# SCH_Moonshine_std_2026-02-26.net
KiCad netlist of a schematic drawn in EasyEDA
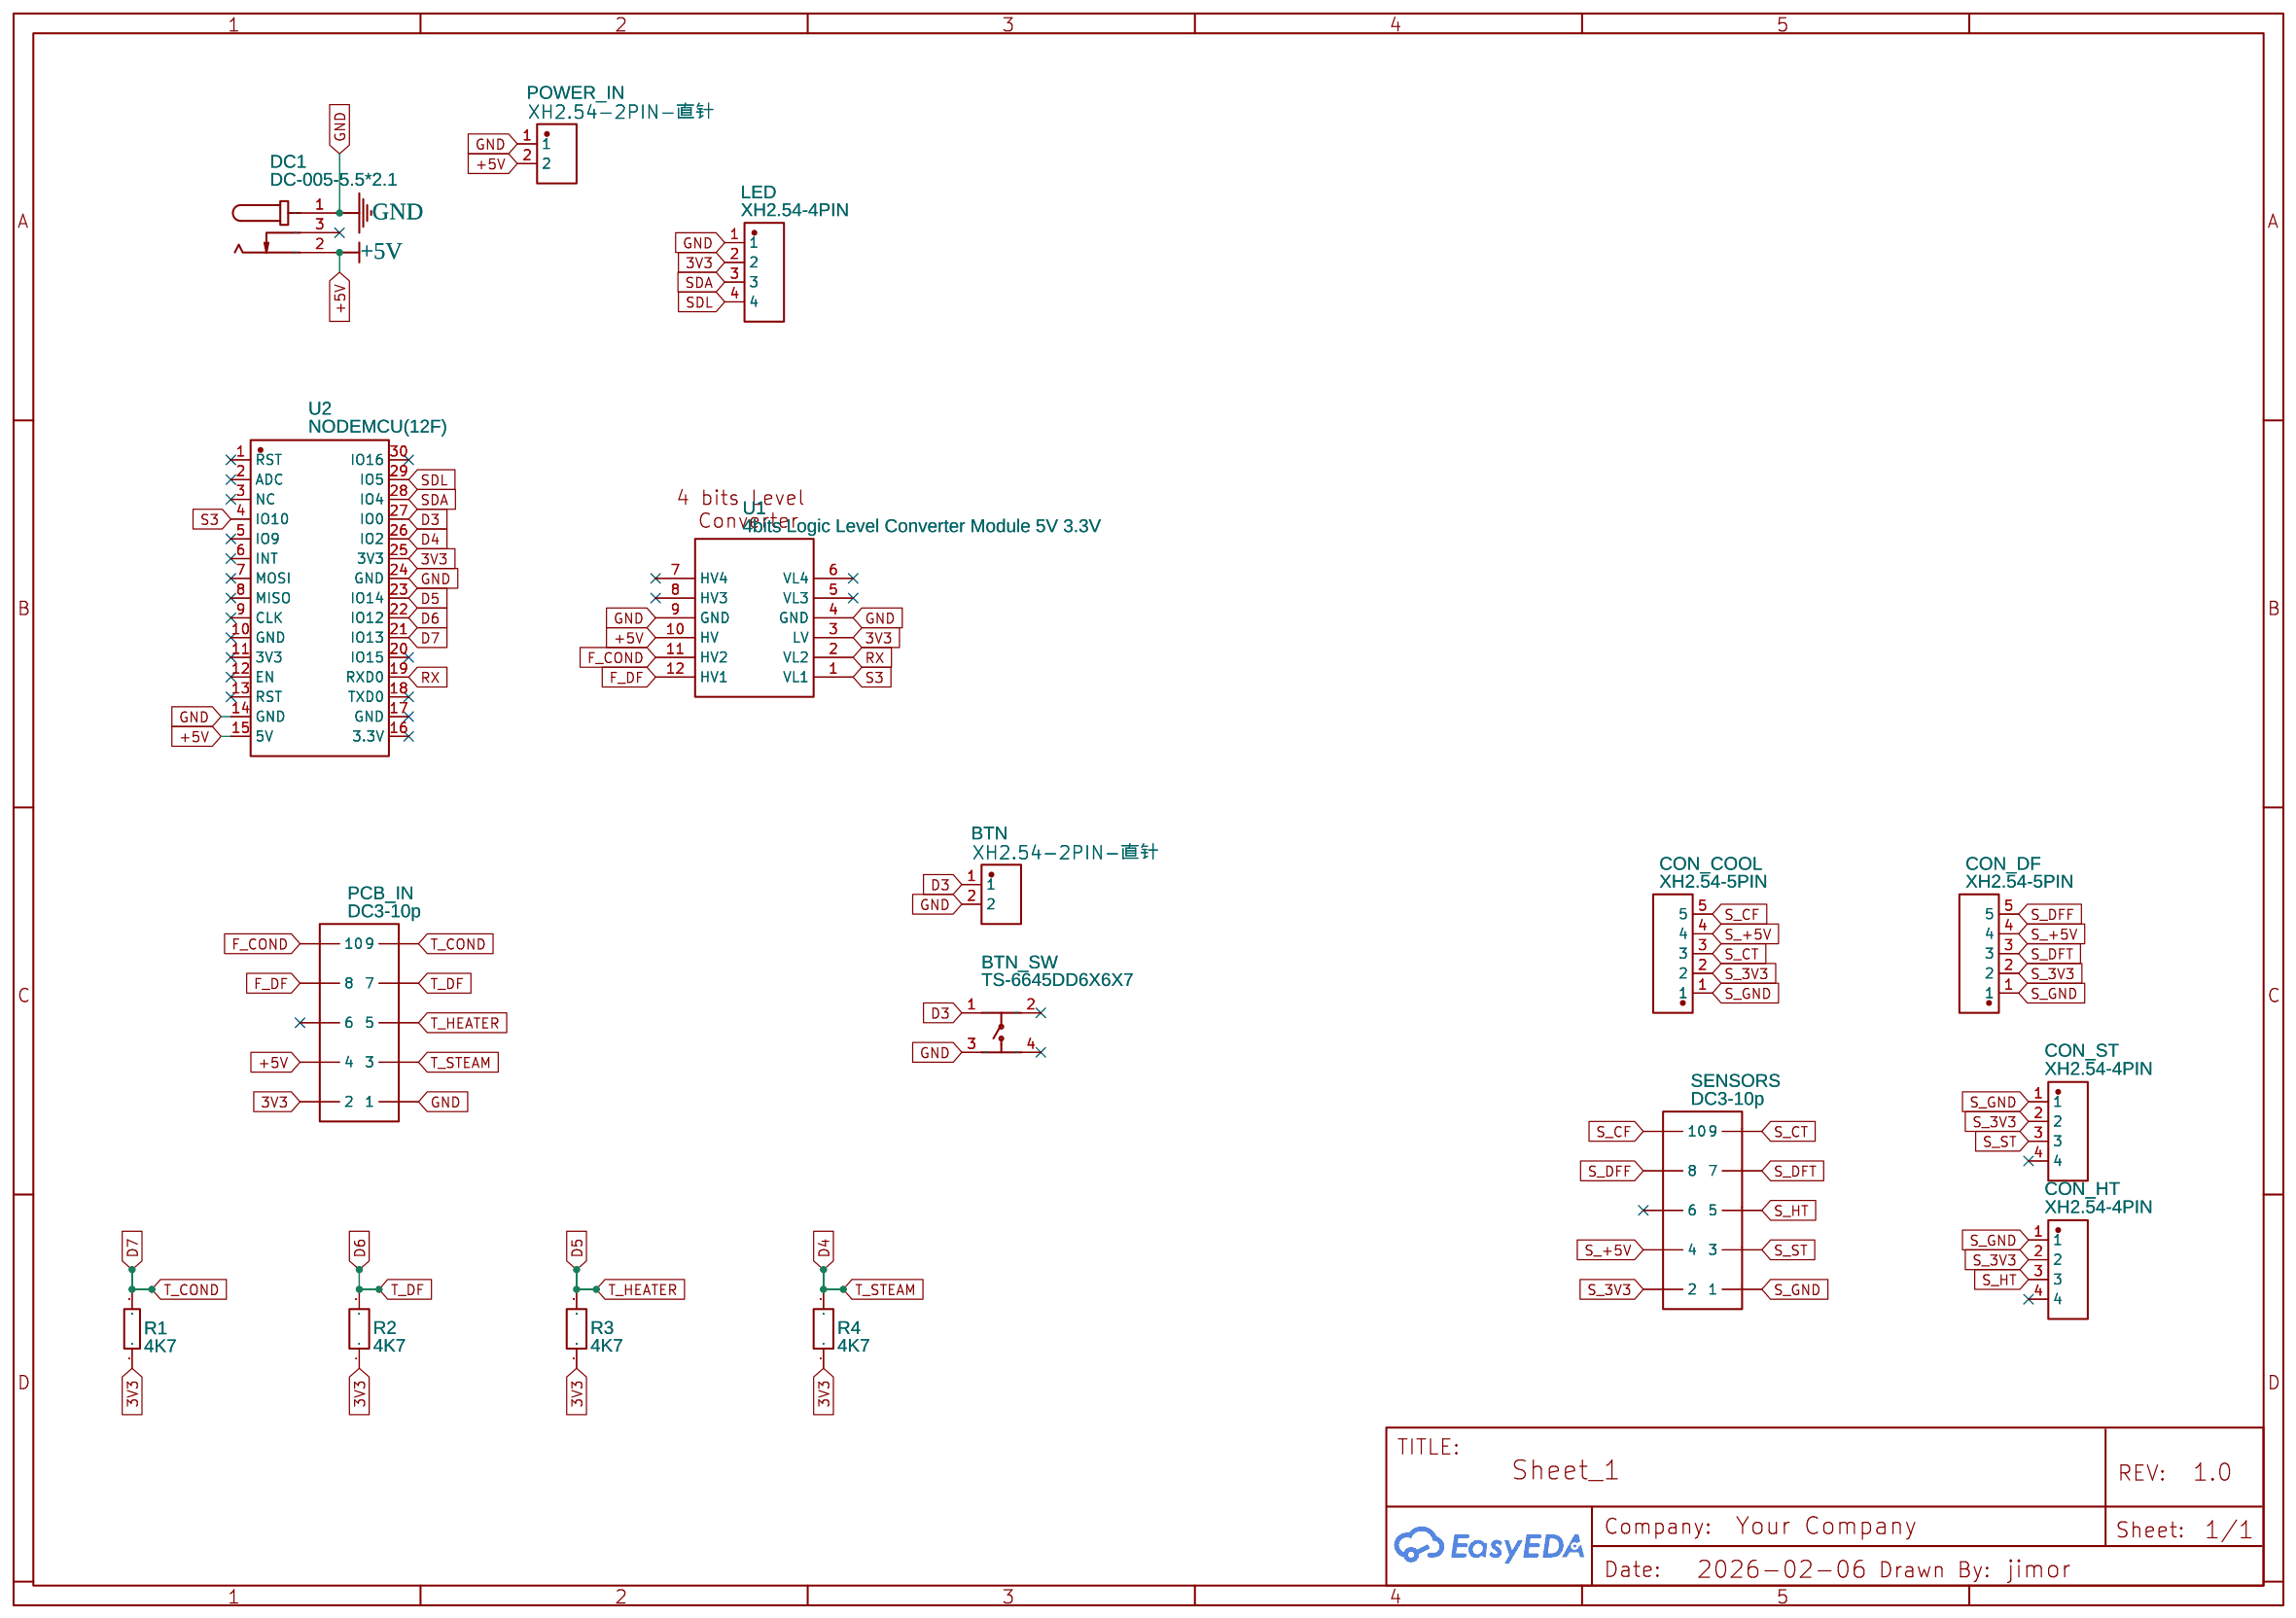
[diagram p0: schematic sheet]

(export (version "E")
  (design (tool "Eeschema 10.0.6"))
  (components
    (comp (ref "BTN") (value "XH2.54-2PIN-直针") (libsource (lib "") (part "XH2.54-2PIN-直针_1")))
    (comp (ref "BTN_SW")
      (value "TS-6645DD6X6X7")
      (fields (field (name "Manufacturer Part") "TS-6645DD6x6x7") (field (name "Manufacturer") "CAX(创都)"))
      (libsource (lib "") (part "TS-6645DD6X6X7"))
    )
    (comp (ref "CON_COOL")
      (value "XH2.54-5PIN")
      (fields (field (name "Manufacturer Part") "PZ254V-11-05P") (field (name "Manufacturer") "XFCN(兴飞)"))
      (libsource (lib "") (part "HDR-TH-2.54-1ROW-5PIN-39MIL-FRUITLOOP57"))
    )
    (comp (ref "CON_DF")
      (value "XH2.54-5PIN")
      (fields (field (name "Manufacturer Part") "PZ254V-11-05P") (field (name "Manufacturer") "XFCN(兴飞)"))
      (libsource (lib "") (part "HDR-TH-2.54-1ROW-5PIN-39MIL-FRUITLOOP57_1"))
    )
    (comp (ref "CON_HT") (value "XH2.54-4PIN") (libsource (lib "") (part "XH2.54-4PIN")))
    (comp (ref "CON_ST") (value "XH2.54-4PIN") (libsource (lib "") (part "XH2.54-4PIN_1")))
    (comp (ref "DC1") (value "DC-005-5.5*2.1") (libsource (lib "") (part "DC-005-5.5*2.1")))
    (comp (ref "LED") (value "XH2.54-4PIN") (libsource (lib "") (part "XH2.54-4PIN_2")))
    (comp (ref "PCB_IN") (value "DC3-10p") (libsource (lib "") (part "DC3-10p_1")))
    (comp (ref "POWER_IN") (value "XH2.54-2PIN-直针") (libsource (lib "") (part "XH2.54-2PIN-直针")))
    (comp (ref "R1")
      (value "4K7")
      (fields (field (name "Manufacturer Part") "AXIAL-0.4"))
      (libsource (lib "") (part "AXIAL-0.4"))
    )
    (comp (ref "R2")
      (value "4K7")
      (fields (field (name "Manufacturer Part") "3.3K-AXIAL-3.0") (field (name "Manufacturer") "睿思电阻"))
      (libsource (lib "") (part "3.3K-AXIAL-3.0"))
    )
    (comp (ref "R3")
      (value "4K7")
      (fields (field (name "Manufacturer Part") "3.3K-AXIAL-3.0") (field (name "Manufacturer") "睿思电阻"))
      (libsource (lib "") (part "3.3K-AXIAL-3.0"))
    )
    (comp (ref "R4")
      (value "4K7")
      (fields (field (name "Manufacturer Part") "3.3K-AXIAL-3.0") (field (name "Manufacturer") "睿思电阻"))
      (libsource (lib "") (part "3.3K-AXIAL-3.0"))
    )
    (comp (ref "SENSORS") (value "DC3-10p") (libsource (lib "") (part "DC3-10p")))
    (comp (ref "U1")
      (value "4bits Logic Level Converter Module 5V 3.3V")
      (libsource (lib "") (part "4bits Logic Level Converter Module 5V 3.3V"))
    )
    (comp (ref "U2")
      (value "NODEMCU(12F)")
      (fields (field (name "Manufacturer") "Ai-Thinker(安信可)"))
      (libsource (lib "") (part "NODEMCU(12F)"))
    )
  )
  (nets
    (net (code "1") (name "+5V") (class "Default")
      (node (ref "DC1") (pin "2") (pinfunction "2_2") (pintype "unspecified"))
      (node (ref "PCB_IN") (pin "4") (pinfunction "4_4") (pintype "unspecified"))
      (node (ref "POWER_IN") (pin "2") (pinfunction "2_2") (pintype "unspecified"))
      (node (ref "U1") (pin "10") (pinfunction "HV_10") (pintype "unspecified"))
      (node (ref "U2") (pin "15") (pinfunction "5V_15") (pintype "unspecified"))
    )
    (net (code "2") (name "3V3") (class "Default")
      (node (ref "LED") (pin "2") (pinfunction "2_2") (pintype "unspecified"))
      (node (ref "PCB_IN") (pin "2") (pinfunction "2_2") (pintype "unspecified"))
      (node (ref "R1") (pin "1") (pinfunction "1_1") (pintype "unspecified"))
      (node (ref "R2") (pin "1") (pinfunction "1_1") (pintype "unspecified"))
      (node (ref "R3") (pin "1") (pinfunction "1_1") (pintype "unspecified"))
      (node (ref "R4") (pin "1") (pinfunction "1_1") (pintype "unspecified"))
      (node (ref "U1") (pin "3") (pinfunction "LV_3") (pintype "unspecified"))
      (node (ref "U2") (pin "25") (pinfunction "3V3_25") (pintype "unspecified"))
    )
    (net (code "3") (name "D3") (class "Default")
      (node (ref "BTN") (pin "1") (pinfunction "1_1") (pintype "unspecified"))
      (node (ref "BTN_SW") (pin "1") (pinfunction "1_1") (pintype "unspecified"))
      (node (ref "U2") (pin "27") (pinfunction "IO0_27") (pintype "unspecified"))
    )
    (net (code "4") (name "D4") (class "Default")
      (node (ref "PCB_IN") (pin "3") (pinfunction "3_3") (pintype "unspecified"))
      (node (ref "R4") (pin "2") (pinfunction "2_2") (pintype "unspecified"))
      (node (ref "U2") (pin "26") (pinfunction "IO2_26") (pintype "unspecified"))
    )
    (net (code "5") (name "D5") (class "Default")
      (node (ref "PCB_IN") (pin "5") (pinfunction "5_5") (pintype "unspecified"))
      (node (ref "R3") (pin "2") (pinfunction "2_2") (pintype "unspecified"))
      (node (ref "U2") (pin "23") (pinfunction "IO14_23") (pintype "unspecified"))
    )
    (net (code "6") (name "D6") (class "Default")
      (node (ref "PCB_IN") (pin "7") (pinfunction "7_7") (pintype "unspecified"))
      (node (ref "R2") (pin "2") (pinfunction "2_2") (pintype "unspecified"))
      (node (ref "U2") (pin "22") (pinfunction "IO12_22") (pintype "unspecified"))
    )
    (net (code "7") (name "D7") (class "Default")
      (node (ref "PCB_IN") (pin "9") (pinfunction "9_9") (pintype "unspecified"))
      (node (ref "R1") (pin "2") (pinfunction "2_2") (pintype "unspecified"))
      (node (ref "U2") (pin "21") (pinfunction "IO13_21") (pintype "unspecified"))
    )
    (net (code "8") (name "F_COND") (class "Default")
      (node (ref "PCB_IN") (pin "10") (pinfunction "10_10") (pintype "unspecified"))
      (node (ref "U1") (pin "11") (pinfunction "HV2_11") (pintype "unspecified"))
    )
    (net (code "9") (name "F_DF") (class "Default")
      (node (ref "PCB_IN") (pin "8") (pinfunction "8_8") (pintype "unspecified"))
      (node (ref "U1") (pin "12") (pinfunction "HV1_12") (pintype "unspecified"))
    )
    (net (code "10") (name "GND") (class "Default")
      (node (ref "BTN") (pin "2") (pinfunction "2_2") (pintype "unspecified"))
      (node (ref "BTN_SW") (pin "3") (pinfunction "3_3") (pintype "unspecified"))
      (node (ref "DC1") (pin "1") (pinfunction "1_1") (pintype "unspecified"))
      (node (ref "LED") (pin "1") (pinfunction "1_1") (pintype "unspecified"))
      (node (ref "PCB_IN") (pin "1") (pinfunction "1_1") (pintype "unspecified"))
      (node (ref "POWER_IN") (pin "1") (pinfunction "1_1") (pintype "unspecified"))
      (node (ref "U1") (pin "4") (pinfunction "GND_4") (pintype "unspecified"))
      (node (ref "U1") (pin "9") (pinfunction "GND_9") (pintype "unspecified"))
      (node (ref "U2") (pin "14") (pinfunction "GND_14") (pintype "unspecified"))
      (node (ref "U2") (pin "24") (pinfunction "GND_24") (pintype "unspecified"))
    )
    (net (code "11") (name "RX") (class "Default")
      (node (ref "U1") (pin "2") (pinfunction "VL2_2") (pintype "unspecified"))
      (node (ref "U2") (pin "19") (pinfunction "RXD0_19") (pintype "unspecified"))
    )
    (net (code "12") (name "S3") (class "Default")
      (node (ref "U1") (pin "1") (pinfunction "VL1_1") (pintype "unspecified"))
      (node (ref "U2") (pin "4") (pinfunction "IO10_4") (pintype "unspecified"))
    )
    (net (code "13") (name "SDA") (class "Default")
      (node (ref "LED") (pin "3") (pinfunction "3_3") (pintype "unspecified"))
      (node (ref "U2") (pin "28") (pinfunction "IO4_28") (pintype "unspecified"))
    )
    (net (code "14") (name "SDL") (class "Default")
      (node (ref "LED") (pin "4") (pinfunction "4_4") (pintype "unspecified"))
      (node (ref "U2") (pin "29") (pinfunction "IO5_29") (pintype "unspecified"))
    )
    (net (code "15") (name "S_+5V") (class "Default")
      (node (ref "CON_COOL") (pin "4") (pinfunction "4_4") (pintype "unspecified"))
      (node (ref "CON_DF") (pin "4") (pinfunction "4_4") (pintype "unspecified"))
      (node (ref "SENSORS") (pin "4") (pinfunction "4_4") (pintype "unspecified"))
    )
    (net (code "16") (name "S_3V3") (class "Default")
      (node (ref "CON_COOL") (pin "2") (pinfunction "2_2") (pintype "unspecified"))
      (node (ref "CON_DF") (pin "2") (pinfunction "2_2") (pintype "unspecified"))
      (node (ref "CON_HT") (pin "2") (pinfunction "2_2") (pintype "unspecified"))
      (node (ref "CON_ST") (pin "2") (pinfunction "2_2") (pintype "unspecified"))
      (node (ref "SENSORS") (pin "2") (pinfunction "2_2") (pintype "unspecified"))
    )
    (net (code "17") (name "S_CF") (class "Default")
      (node (ref "CON_COOL") (pin "5") (pinfunction "5_5") (pintype "unspecified"))
      (node (ref "SENSORS") (pin "10") (pinfunction "10_10") (pintype "unspecified"))
    )
    (net (code "18") (name "S_CT") (class "Default")
      (node (ref "CON_COOL") (pin "3") (pinfunction "3_3") (pintype "unspecified"))
      (node (ref "SENSORS") (pin "9") (pinfunction "9_9") (pintype "unspecified"))
    )
    (net (code "19") (name "S_DFF") (class "Default")
      (node (ref "CON_DF") (pin "5") (pinfunction "5_5") (pintype "unspecified"))
      (node (ref "SENSORS") (pin "8") (pinfunction "8_8") (pintype "unspecified"))
    )
    (net (code "20") (name "S_DFT") (class "Default")
      (node (ref "CON_DF") (pin "3") (pinfunction "3_3") (pintype "unspecified"))
      (node (ref "SENSORS") (pin "7") (pinfunction "7_7") (pintype "unspecified"))
    )
    (net (code "21") (name "S_GND") (class "Default")
      (node (ref "CON_COOL") (pin "1") (pinfunction "1_1") (pintype "unspecified"))
      (node (ref "CON_DF") (pin "1") (pinfunction "1_1") (pintype "unspecified"))
      (node (ref "CON_HT") (pin "1") (pinfunction "1_1") (pintype "unspecified"))
      (node (ref "CON_ST") (pin "1") (pinfunction "1_1") (pintype "unspecified"))
      (node (ref "SENSORS") (pin "1") (pinfunction "1_1") (pintype "unspecified"))
    )
    (net (code "22") (name "S_HT") (class "Default")
      (node (ref "CON_HT") (pin "3") (pinfunction "3_3") (pintype "unspecified"))
      (node (ref "SENSORS") (pin "5") (pinfunction "5_5") (pintype "unspecified"))
    )
    (net (code "23") (name "S_ST") (class "Default")
      (node (ref "CON_ST") (pin "3") (pinfunction "3_3") (pintype "unspecified"))
      (node (ref "SENSORS") (pin "3") (pinfunction "3_3") (pintype "unspecified"))
    )
    (net (code "24") (name "unconnected-(BTN_SW-Pad2)") (class "Default")
      (node (ref "BTN_SW") (pin "2") (pinfunction "2_2") (pintype "unspecified+no_connect"))
    )
    (net (code "25") (name "unconnected-(BTN_SW-Pad4)") (class "Default")
      (node (ref "BTN_SW") (pin "4") (pinfunction "4_4") (pintype "unspecified+no_connect"))
    )
    (net (code "26") (name "unconnected-(CON_HT-Pad4)") (class "Default")
      (node (ref "CON_HT") (pin "4") (pinfunction "4_4") (pintype "unspecified+no_connect"))
    )
    (net (code "27") (name "unconnected-(CON_ST-Pad4)") (class "Default")
      (node (ref "CON_ST") (pin "4") (pinfunction "4_4") (pintype "unspecified+no_connect"))
    )
    (net (code "28") (name "unconnected-(DC1-Pad3)") (class "Default")
      (node (ref "DC1") (pin "3") (pinfunction "3_3") (pintype "unspecified+no_connect"))
    )
    (net (code "29") (name "unconnected-(PCB_IN-Pad6)") (class "Default")
      (node (ref "PCB_IN") (pin "6") (pinfunction "6_6") (pintype "unspecified+no_connect"))
    )
    (net (code "30") (name "unconnected-(SENSORS-Pad6)") (class "Default")
      (node (ref "SENSORS") (pin "6") (pinfunction "6_6") (pintype "unspecified+no_connect"))
    )
    (net (code "31") (name "unconnected-(U1-HV3-Pad8)") (class "Default")
      (node (ref "U1") (pin "8") (pinfunction "HV3_8") (pintype "unspecified+no_connect"))
    )
    (net (code "32") (name "unconnected-(U1-HV4-Pad7)") (class "Default")
      (node (ref "U1") (pin "7") (pinfunction "HV4_7") (pintype "unspecified+no_connect"))
    )
    (net (code "33") (name "unconnected-(U1-VL3-Pad5)") (class "Default")
      (node (ref "U1") (pin "5") (pinfunction "VL3_5") (pintype "unspecified+no_connect"))
    )
    (net (code "34") (name "unconnected-(U1-VL4-Pad6)") (class "Default")
      (node (ref "U1") (pin "6") (pinfunction "VL4_6") (pintype "unspecified+no_connect"))
    )
    (net (code "35") (name "unconnected-(U2-3.3V-Pad16)") (class "Default")
      (node (ref "U2") (pin "16") (pinfunction "3.3V_16") (pintype "unspecified+no_connect"))
    )
    (net (code "36") (name "unconnected-(U2-3V3-Pad11)") (class "Default")
      (node (ref "U2") (pin "11") (pinfunction "3V3_11") (pintype "unspecified+no_connect"))
    )
    (net (code "37") (name "unconnected-(U2-ADC-Pad2)") (class "Default")
      (node (ref "U2") (pin "2") (pinfunction "ADC_2") (pintype "unspecified+no_connect"))
    )
    (net (code "38") (name "unconnected-(U2-CLK-Pad9)") (class "Default")
      (node (ref "U2") (pin "9") (pinfunction "CLK_9") (pintype "unspecified+no_connect"))
    )
    (net (code "39") (name "unconnected-(U2-EN-Pad12)") (class "Default")
      (node (ref "U2") (pin "12") (pinfunction "EN_12") (pintype "unspecified+no_connect"))
    )
    (net (code "40") (name "unconnected-(U2-GND-Pad10)") (class "Default")
      (node (ref "U2") (pin "10") (pinfunction "GND_10") (pintype "unspecified+no_connect"))
    )
    (net (code "41") (name "unconnected-(U2-GND-Pad17)") (class "Default")
      (node (ref "U2") (pin "17") (pinfunction "GND_17") (pintype "unspecified+no_connect"))
    )
    (net (code "42") (name "unconnected-(U2-INT-Pad6)") (class "Default")
      (node (ref "U2") (pin "6") (pinfunction "INT_6") (pintype "unspecified+no_connect"))
    )
    (net (code "43") (name "unconnected-(U2-IO9-Pad5)") (class "Default")
      (node (ref "U2") (pin "5") (pinfunction "IO9_5") (pintype "unspecified+no_connect"))
    )
    (net (code "44") (name "unconnected-(U2-IO15-Pad20)") (class "Default")
      (node (ref "U2") (pin "20") (pinfunction "IO15_20") (pintype "unspecified+no_connect"))
    )
    (net (code "45") (name "unconnected-(U2-IO16-Pad30)") (class "Default")
      (node (ref "U2") (pin "30") (pinfunction "IO16_30") (pintype "unspecified+no_connect"))
    )
    (net (code "46") (name "unconnected-(U2-MISO-Pad8)") (class "Default")
      (node (ref "U2") (pin "8") (pinfunction "MISO_8") (pintype "unspecified+no_connect"))
    )
    (net (code "47") (name "unconnected-(U2-MOSI-Pad7)") (class "Default")
      (node (ref "U2") (pin "7") (pinfunction "MOSI_7") (pintype "unspecified+no_connect"))
    )
    (net (code "48") (name "unconnected-(U2-NC-Pad3)") (class "Default")
      (node (ref "U2") (pin "3") (pinfunction "NC_3") (pintype "unspecified+no_connect"))
    )
    (net (code "49") (name "unconnected-(U2-RST-Pad1)") (class "Default")
      (node (ref "U2") (pin "1") (pinfunction "RST_1") (pintype "unspecified+no_connect"))
    )
    (net (code "50") (name "unconnected-(U2-RST-Pad13)") (class "Default")
      (node (ref "U2") (pin "13") (pinfunction "RST_13") (pintype "unspecified+no_connect"))
    )
    (net (code "51") (name "unconnected-(U2-TXD0-Pad18)") (class "Default")
      (node (ref "U2") (pin "18") (pinfunction "TXD0_18") (pintype "unspecified+no_connect"))
    )
  )
)
